# SCH_Samvid-Hacker-Card-3_2025-08-04.net
KiCad netlist of a schematic drawn in EasyEDA
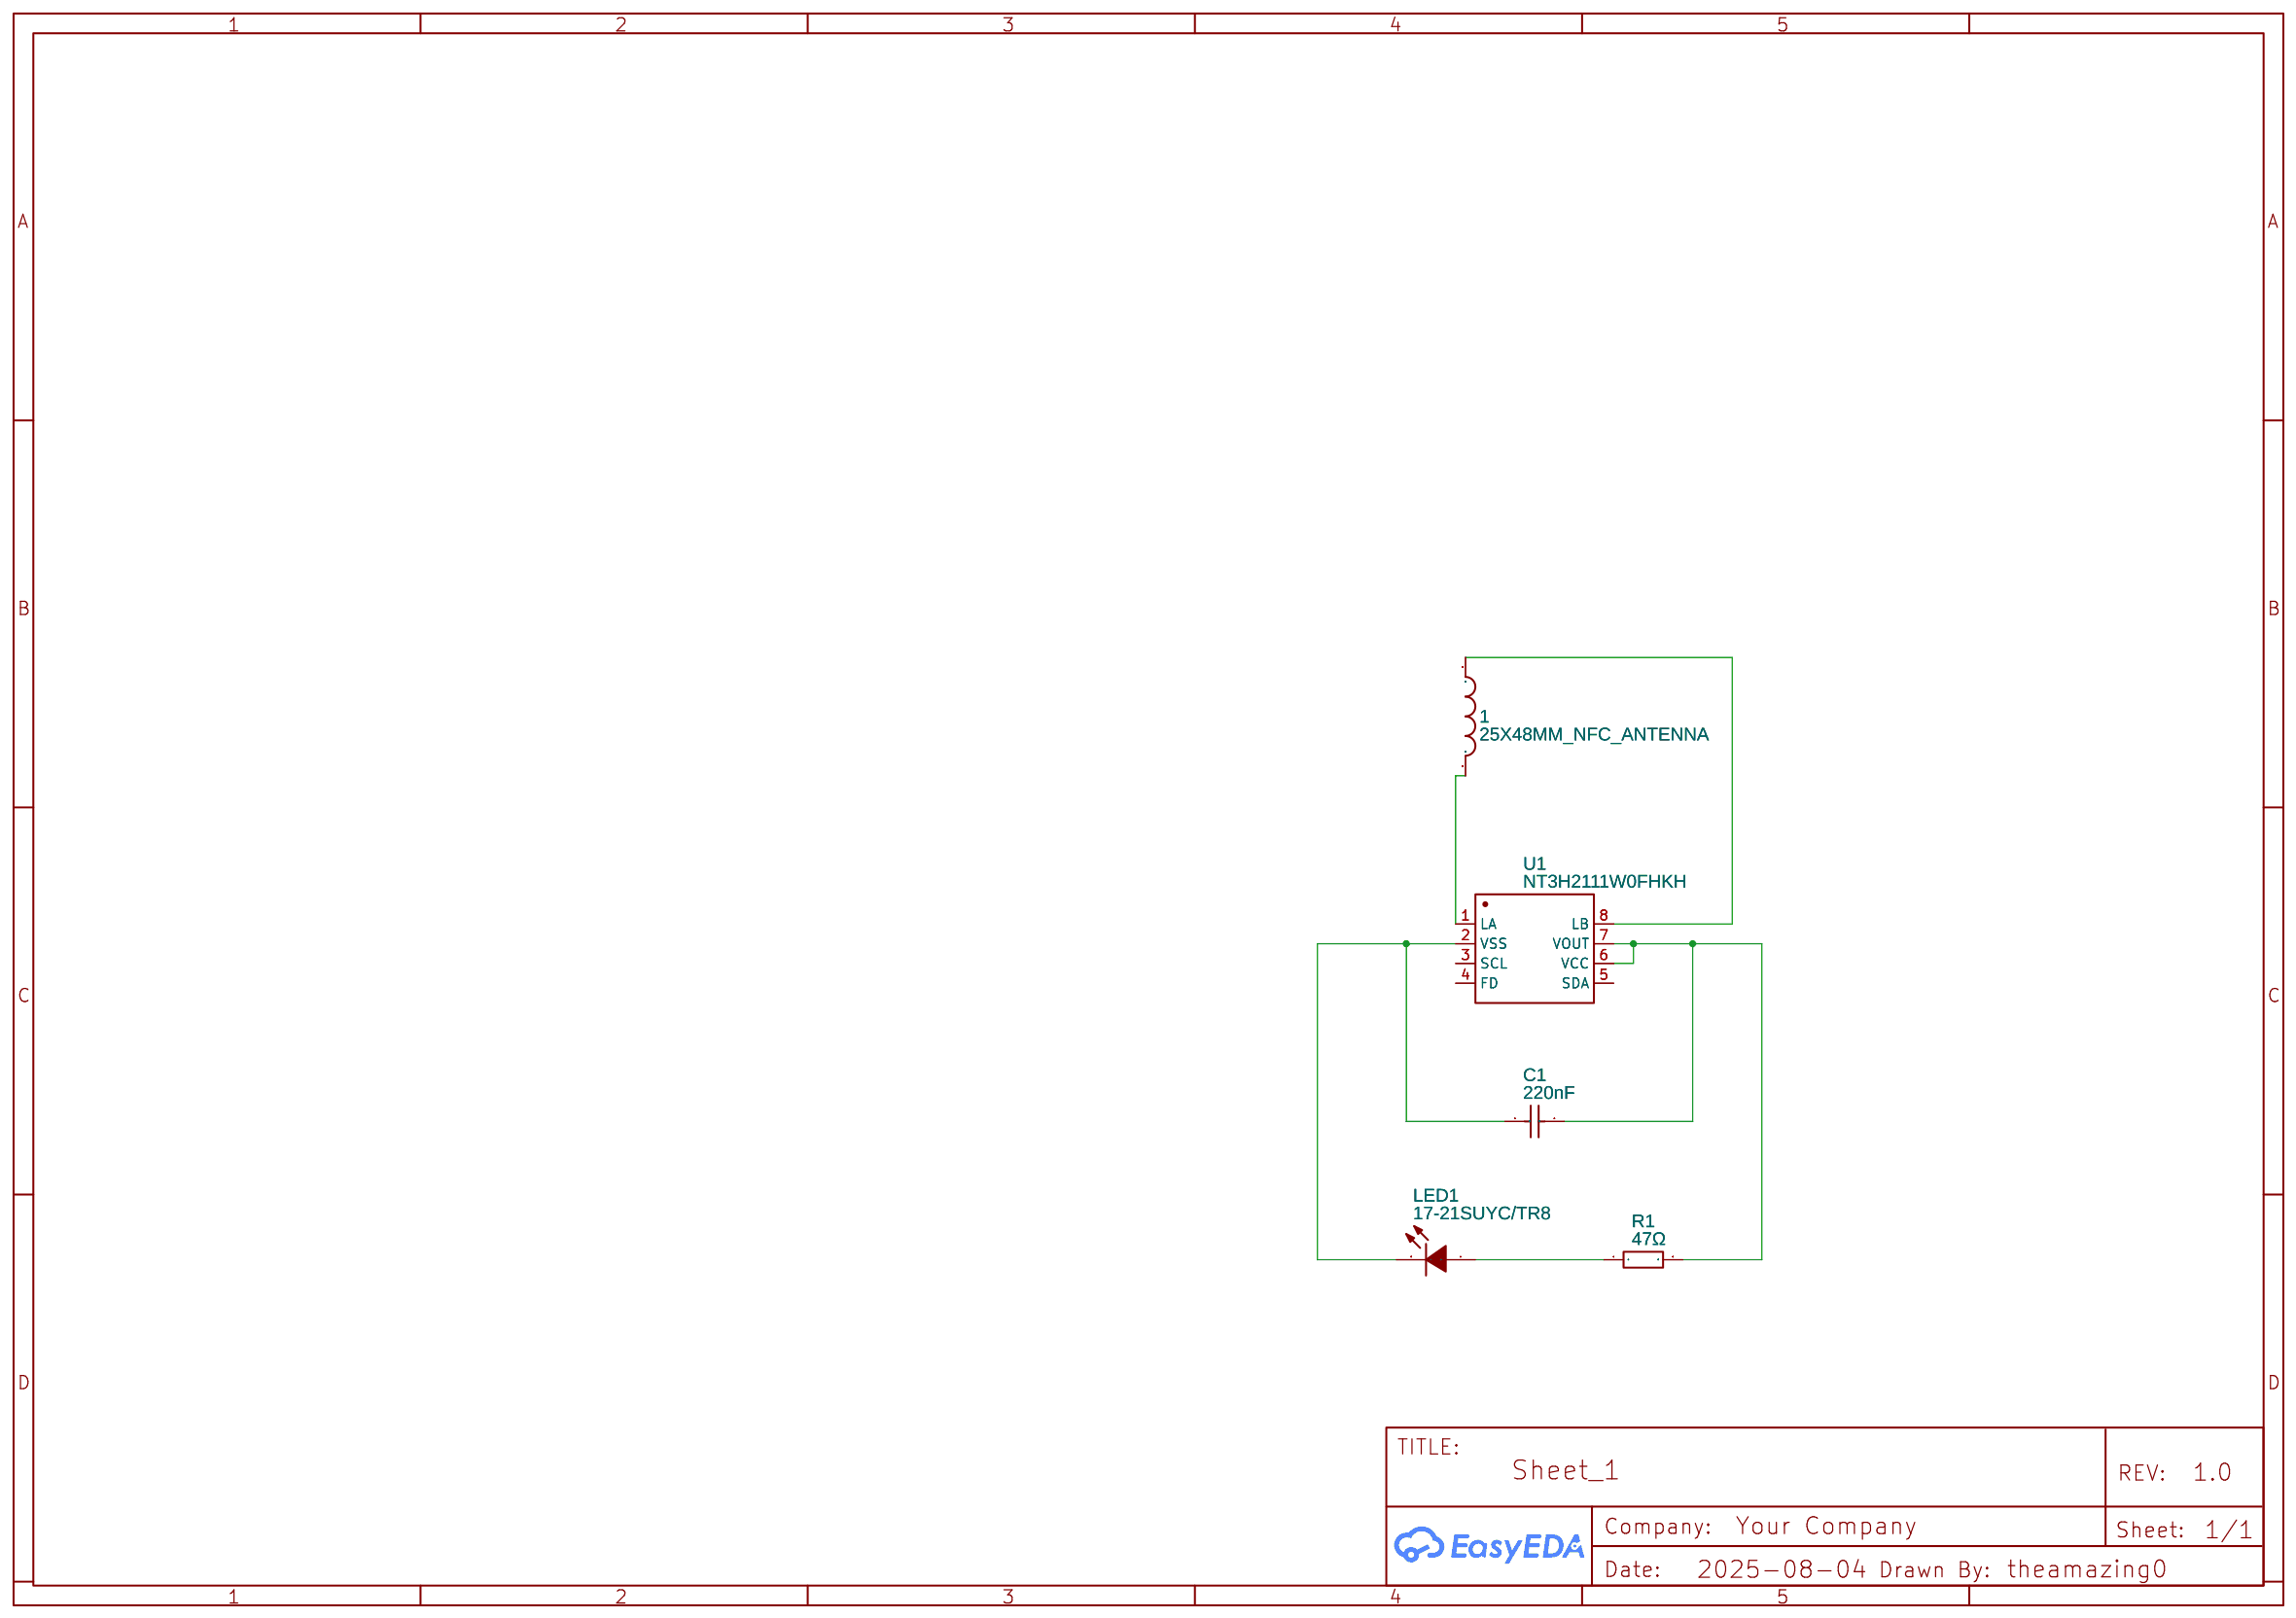
[diagram p0: schematic sheet]

(export (version "E")
  (design (tool "Eeschema 10.0.6"))
  (components
    (comp (ref "1") (value "25X48MM_NFC_ANTENNA") (libsource (lib "") (part "25X48MM_NFC_ANTENNA")))
    (comp (ref "C1")
      (value "220nF")
      (fields
        (field (name "Manufacturer Part") "CL10B224KA8NNNC")
        (field (name "Manufacturer") "SAMSUNG(三星)")
      )
      (libsource (lib "") (part "CL10B224KA8NNNC"))
    )
    (comp (ref "LED1")
      (value "17-21SUYC/TR8")
      (fields (field (name "Manufacturer Part") "KT-0805黄灯") (field (name "Manufacturer") "KENTO"))
      (libsource (lib "") (part "17-21SUYC/TR8"))
    )
    (comp (ref "R1")
      (value "47Ω")
      (fields
        (field (name "Manufacturer Part") "0603WAF470JT5E")
        (field (name "Manufacturer") "UNI-ROYAL(厚声)")
      )
      (libsource (lib "") (part "0603WAF470JT5E"))
    )
    (comp (ref "U1")
      (value "NT3H2111W0FHKH")
      (fields (field (name "Manufacturer") "NXP(恩智浦)"))
      (libsource (lib "") (part "NT3H2111W0FHKH"))
    )
  )
  (nets
    (net (code "1") (name "Net-(LED1-+)") (class "Default")
      (node (ref "LED1") (pin "1") (pinfunction "+_1") (pintype "unspecified"))
      (node (ref "R1") (pin "1") (pinfunction "1_1") (pintype "input"))
    )
    (net (code "2") (name "Net-(LED1--)") (class "Default")
      (node (ref "C1") (pin "1") (pinfunction "1_1") (pintype "input"))
      (node (ref "LED1") (pin "2") (pinfunction "-_2") (pintype "unspecified"))
      (node (ref "U1") (pin "2") (pinfunction "VSS_2") (pintype "unspecified"))
    )
    (net (code "3") (name "Net-(U1-LA)") (class "Default")
      (node (ref "1") (pin "P$2") (pinfunction "P$2_P$2") (pintype "bidirectional"))
      (node (ref "U1") (pin "1") (pinfunction "LA_1") (pintype "unspecified"))
    )
    (net (code "4") (name "Net-(U1-LB)") (class "Default")
      (node (ref "1") (pin "P$1") (pinfunction "P$1_P$1") (pintype "bidirectional"))
      (node (ref "U1") (pin "8") (pinfunction "LB_8") (pintype "unspecified"))
    )
    (net (code "5") (name "Net-(U1-VCC)") (class "Default")
      (node (ref "C1") (pin "2") (pinfunction "2_2") (pintype "input"))
      (node (ref "R1") (pin "2") (pinfunction "2_2") (pintype "input"))
      (node (ref "U1") (pin "6") (pinfunction "VCC_6") (pintype "unspecified"))
      (node (ref "U1") (pin "7") (pinfunction "VOUT_7") (pintype "unspecified"))
    )
    (net (code "6") (name "unconnected-(U1-FD-Pad4)") (class "Default")
      (node (ref "U1") (pin "4") (pinfunction "FD_4") (pintype "unspecified"))
    )
    (net (code "7") (name "unconnected-(U1-SCL-Pad3)") (class "Default")
      (node (ref "U1") (pin "3") (pinfunction "SCL_3") (pintype "unspecified"))
    )
    (net (code "8") (name "unconnected-(U1-SDA-Pad5)") (class "Default")
      (node (ref "U1") (pin "5") (pinfunction "SDA_5") (pintype "unspecified"))
    )
  )
)
